# SOIL_WATER.net
KiCad netlist of a schematic drawn in EAGLE
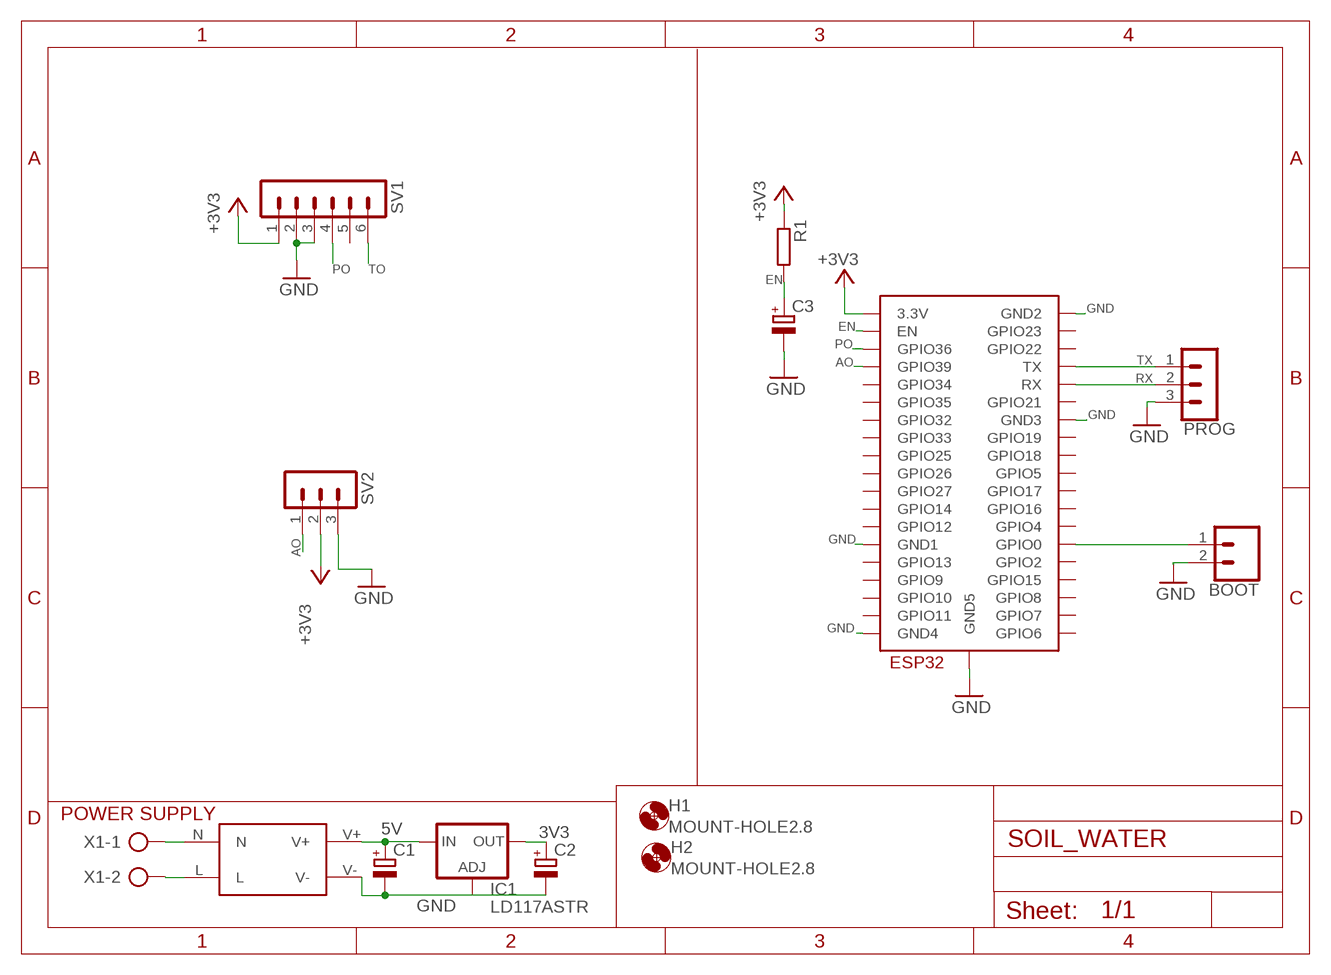
[diagram p0: schematic, sheet 1]

(export (version "E")
  (design (tool "Eeschema 10.0.6"))
  (components
    (comp (ref "BOOT")
      (value "CONN_02")
      (footprint "eagle-import:1X02")
      (libsource (lib "eagle-import") (part "CONN_02"))
    )
    (comp (ref "C1")
      (value "CPOL-EUE1.8-4")
      (footprint "eagle-import:E1,8-4")
      (libsource (lib "eagle-import") (part "CPOL-EUE1.8-4"))
    )
    (comp (ref "C2")
      (value "CPOL-EUE1.8-4")
      (footprint "eagle-import:E1,8-4")
      (libsource (lib "eagle-import") (part "CPOL-EUE1.8-4"))
    )
    (comp (ref "C3")
      (value "CPOL-EUE1.8-4")
      (footprint "eagle-import:E1,8-4")
      (libsource (lib "eagle-import") (part "CPOL-EUE1.8-4"))
    )
    (comp (ref "H1")
      (value "MOUNT-HOLE2.8")
      (footprint "eagle-import:2,8")
      (libsource (lib "eagle-import") (part "MOUNT-HOLE2.8"))
    )
    (comp (ref "H2")
      (value "MOUNT-HOLE2.8")
      (footprint "eagle-import:2,8")
      (libsource (lib "eagle-import") (part "MOUNT-HOLE2.8"))
    )
    (comp (ref "IC1")
      (value "LD117ASTR")
      (footprint "eagle-import:SOT223")
      (libsource (lib "eagle-import") (part "LD117A?STR"))
    )
    (comp (ref "PROG")
      (value "MA03-1")
      (footprint "eagle-import:MA03-1")
      (libsource (lib "eagle-import") (part "MA03-1"))
    )
    (comp (ref "R1")
      (value "R-EU_0204/7")
      (footprint "eagle-import:0204_7")
      (libsource (lib "eagle-import") (part "R-EU_0204/7"))
    )
    (comp (ref "SV1")
      (value "MA06-1")
      (footprint "eagle-import:MA06-1")
      (libsource (lib "eagle-import") (part "MA06-1"))
    )
    (comp (ref "SV2")
      (value "MA03-1")
      (footprint "eagle-import:MA03-1")
      (libsource (lib "eagle-import") (part "MA03-1"))
    )
    (comp (ref "U$1")
      (value "ESP32-WROOM")
      (footprint "eagle-import:ESP32-WROOM")
      (libsource (lib "eagle-import") (part "ESP32-WROOM"))
    )
    (comp (ref "U$2")
      (value "HLK-PM01")
      (footprint "eagle-import:HLK-PM01-PAK")
      (fields (field (name "MF") "Hi-link") (field (name "MP") "hlk-pm01"))
      (libsource (lib "eagle-import") (part "HLK-PM01"))
    )
    (comp (ref "X1")
      (value "AK500/2")
      (footprint "eagle-import:AK500_2")
      (libsource (lib "eagle-import") (part "AK500/2"))
    )
  )
  (nets
    (net (code "1") (name "+3V3") (class "Default")
      (node (ref "R1") (pin "1") (pinfunction "1_1") (pintype "passive"))
      (node (ref "SV1") (pin "1") (pinfunction "1_1") (pintype "passive"))
      (node (ref "SV2") (pin "2") (pinfunction "2_2") (pintype "passive"))
      (node (ref "U$1") (pin "3V3") (pinfunction "3.3V_3V3") (pintype "bidirectional"))
    )
    (net (code "2") (name "/3V3") (class "Default")
      (node (ref "C2") (pin "+") (pinfunction "+_+") (pintype "passive"))
      (node (ref "IC1") (pin "4") (pinfunction "OUT_4") (pintype "passive"))
    )
    (net (code "3") (name "/5V") (class "Default")
      (node (ref "C1") (pin "+") (pinfunction "+_+") (pintype "passive"))
      (node (ref "IC1") (pin "3") (pinfunction "IN_3") (pintype "input"))
      (node (ref "U$2") (pin "V+") (pinfunction "V+_V+") (pintype "bidirectional"))
    )
    (net (code "4") (name "/AO") (class "Default")
      (node (ref "SV2") (pin "1") (pinfunction "1_1") (pintype "passive"))
      (node (ref "U$1") (pin "SENSOR_VN") (pinfunction "GPIO39_SENSOR_VN") (pintype "bidirectional"))
    )
    (net (code "5") (name "/EN") (class "Default")
      (node (ref "C3") (pin "+") (pinfunction "+_+") (pintype "passive"))
      (node (ref "R1") (pin "2") (pinfunction "2_2") (pintype "passive"))
      (node (ref "U$1") (pin "EN") (pinfunction "EN_EN") (pintype "bidirectional"))
    )
    (net (code "6") (name "/PO") (class "Default")
      (node (ref "SV1") (pin "4") (pinfunction "4_4") (pintype "passive"))
      (node (ref "U$1") (pin "SENSOR_VP") (pinfunction "GPIO36_SENSOR_VP") (pintype "bidirectional"))
    )
    (net (code "7") (name "/RX") (class "Default")
      (node (ref "PROG") (pin "2") (pinfunction "2_2") (pintype "passive"))
      (node (ref "U$1") (pin "RX") (pinfunction "RX_RX") (pintype "bidirectional"))
    )
    (net (code "8") (name "/TO") (class "Default")
      (node (ref "SV1") (pin "6") (pinfunction "6_6") (pintype "passive"))
    )
    (net (code "9") (name "/TX") (class "Default")
      (node (ref "PROG") (pin "1") (pinfunction "1_1") (pintype "passive"))
      (node (ref "U$1") (pin "TX") (pinfunction "TX_TX") (pintype "bidirectional"))
    )
    (net (code "10") (name "GND") (class "Default")
      (node (ref "BOOT") (pin "2") (pinfunction "2_2") (pintype "passive"))
      (node (ref "C1") (pin "-") (pinfunction "-_-") (pintype "passive"))
      (node (ref "C2") (pin "-") (pinfunction "-_-") (pintype "passive"))
      (node (ref "C3") (pin "-") (pinfunction "-_-") (pintype "passive"))
      (node (ref "IC1") (pin "1") (pinfunction "ADJ_1") (pintype "input"))
      (node (ref "PROG") (pin "3") (pinfunction "3_3") (pintype "passive"))
      (node (ref "SV1") (pin "2") (pinfunction "2_2") (pintype "passive"))
      (node (ref "SV1") (pin "3") (pinfunction "3_3") (pintype "passive"))
      (node (ref "SV2") (pin "3") (pinfunction "3_3") (pintype "passive"))
      (node (ref "U$1") (pin "GND1") (pinfunction "GND1_GND1") (pintype "bidirectional"))
      (node (ref "U$1") (pin "GND2") (pinfunction "GND2_GND2") (pintype "bidirectional"))
      (node (ref "U$1") (pin "GND3") (pinfunction "GND3_GND3") (pintype "bidirectional"))
      (node (ref "U$1") (pin "GND4") (pinfunction "GND4_GND4") (pintype "bidirectional"))
      (node (ref "U$1") (pin "GND5") (pinfunction "GND5_GND5") (pintype "bidirectional"))
      (node (ref "U$2") (pin "V-") (pinfunction "V-_V-") (pintype "bidirectional"))
    )
    (net (code "11") (name "Net-(U$1-GPIO0)") (class "Default")
      (node (ref "BOOT") (pin "1") (pinfunction "1_1") (pintype "passive"))
      (node (ref "U$1") (pin "IO0") (pinfunction "GPIO0_IO0") (pintype "bidirectional"))
    )
    (net (code "12") (name "Net-(X1A-KL)") (class "Default")
      (node (ref "U$2") (pin "N") (pinfunction "N_N") (pintype "bidirectional"))
      (node (ref "X1") (pin "1") (pinfunction "KL_1") (pintype "passive"))
    )
    (net (code "13") (name "Net-(X1B-KL)") (class "Default")
      (node (ref "U$2") (pin "L") (pinfunction "L_L") (pintype "bidirectional"))
      (node (ref "X1") (pin "2") (pinfunction "KL_2") (pintype "passive"))
    )
    (net (code "14") (name "unconnected-(SV1-Pad5)") (class "Default")
      (node (ref "SV1") (pin "5") (pinfunction "5_5") (pintype "passive"))
    )
    (net (code "15") (name "unconnected-(U$1-GPIO2-PadIO2)") (class "Default")
      (node (ref "U$1") (pin "IO2") (pinfunction "GPIO2_IO2") (pintype "bidirectional"))
    )
    (net (code "16") (name "unconnected-(U$1-GPIO4-PadIO4)") (class "Default")
      (node (ref "U$1") (pin "IO4") (pinfunction "GPIO4_IO4") (pintype "bidirectional"))
    )
    (net (code "17") (name "unconnected-(U$1-GPIO5-PadIO5)") (class "Default")
      (node (ref "U$1") (pin "IO5") (pinfunction "GPIO5_IO5") (pintype "bidirectional"))
    )
    (net (code "18") (name "unconnected-(U$1-GPIO6-PadCLK)") (class "Default")
      (node (ref "U$1") (pin "CLK") (pinfunction "GPIO6_CLK") (pintype "bidirectional"))
    )
    (net (code "19") (name "unconnected-(U$1-GPIO7-PadSD0)") (class "Default")
      (node (ref "U$1") (pin "SD0") (pinfunction "GPIO7_SD0") (pintype "bidirectional"))
    )
    (net (code "20") (name "unconnected-(U$1-GPIO8-PadSD1)") (class "Default")
      (node (ref "U$1") (pin "SD1") (pinfunction "GPIO8_SD1") (pintype "bidirectional"))
    )
    (net (code "21") (name "unconnected-(U$1-GPIO9-PadSD2)") (class "Default")
      (node (ref "U$1") (pin "SD2") (pinfunction "GPIO9_SD2") (pintype "bidirectional"))
    )
    (net (code "22") (name "unconnected-(U$1-GPIO10-PadSD3)") (class "Default")
      (node (ref "U$1") (pin "SD3") (pinfunction "GPIO10_SD3") (pintype "bidirectional"))
    )
    (net (code "23") (name "unconnected-(U$1-GPIO11-PadCMD)") (class "Default")
      (node (ref "U$1") (pin "CMD") (pinfunction "GPIO11_CMD") (pintype "bidirectional"))
    )
    (net (code "24") (name "unconnected-(U$1-GPIO12-PadIO12)") (class "Default")
      (node (ref "U$1") (pin "IO12") (pinfunction "GPIO12_IO12") (pintype "bidirectional"))
    )
    (net (code "25") (name "unconnected-(U$1-GPIO13-PadIO13)") (class "Default")
      (node (ref "U$1") (pin "IO13") (pinfunction "GPIO13_IO13") (pintype "bidirectional"))
    )
    (net (code "26") (name "unconnected-(U$1-GPIO14-PadIO14)") (class "Default")
      (node (ref "U$1") (pin "IO14") (pinfunction "GPIO14_IO14") (pintype "bidirectional"))
    )
    (net (code "27") (name "unconnected-(U$1-GPIO15-PadIO15)") (class "Default")
      (node (ref "U$1") (pin "IO15") (pinfunction "GPIO15_IO15") (pintype "bidirectional"))
    )
    (net (code "28") (name "unconnected-(U$1-GPIO16-PadIO16)") (class "Default")
      (node (ref "U$1") (pin "IO16") (pinfunction "GPIO16_IO16") (pintype "bidirectional"))
    )
    (net (code "29") (name "unconnected-(U$1-GPIO17-PadIO17)") (class "Default")
      (node (ref "U$1") (pin "IO17") (pinfunction "GPIO17_IO17") (pintype "bidirectional"))
    )
    (net (code "30") (name "unconnected-(U$1-GPIO18-PadIO18)") (class "Default")
      (node (ref "U$1") (pin "IO18") (pinfunction "GPIO18_IO18") (pintype "bidirectional"))
    )
    (net (code "31") (name "unconnected-(U$1-GPIO19-PadIO19)") (class "Default")
      (node (ref "U$1") (pin "IO19") (pinfunction "GPIO19_IO19") (pintype "bidirectional"))
    )
    (net (code "32") (name "unconnected-(U$1-GPIO21-PadIO21)") (class "Default")
      (node (ref "U$1") (pin "IO21") (pinfunction "GPIO21_IO21") (pintype "bidirectional"))
    )
    (net (code "33") (name "unconnected-(U$1-GPIO22-PadIO22)") (class "Default")
      (node (ref "U$1") (pin "IO22") (pinfunction "GPIO22_IO22") (pintype "bidirectional"))
    )
    (net (code "34") (name "unconnected-(U$1-GPIO23-PadIO23)") (class "Default")
      (node (ref "U$1") (pin "IO23") (pinfunction "GPIO23_IO23") (pintype "bidirectional"))
    )
    (net (code "35") (name "unconnected-(U$1-GPIO25-PadIO25)") (class "Default")
      (node (ref "U$1") (pin "IO25") (pinfunction "GPIO25_IO25") (pintype "bidirectional"))
    )
    (net (code "36") (name "unconnected-(U$1-GPIO26-PadIO26)") (class "Default")
      (node (ref "U$1") (pin "IO26") (pinfunction "GPIO26_IO26") (pintype "bidirectional"))
    )
    (net (code "37") (name "unconnected-(U$1-GPIO27-PadIO27)") (class "Default")
      (node (ref "U$1") (pin "IO27") (pinfunction "GPIO27_IO27") (pintype "bidirectional"))
    )
    (net (code "38") (name "unconnected-(U$1-GPIO32-PadIO32)") (class "Default")
      (node (ref "U$1") (pin "IO32") (pinfunction "GPIO32_IO32") (pintype "bidirectional"))
    )
    (net (code "39") (name "unconnected-(U$1-GPIO33-PadIO33)") (class "Default")
      (node (ref "U$1") (pin "IO33") (pinfunction "GPIO33_IO33") (pintype "bidirectional"))
    )
    (net (code "40") (name "unconnected-(U$1-GPIO34-PadIO34)") (class "Default")
      (node (ref "U$1") (pin "IO34") (pinfunction "GPIO34_IO34") (pintype "bidirectional"))
    )
    (net (code "41") (name "unconnected-(U$1-GPIO35-PadIO35)") (class "Default")
      (node (ref "U$1") (pin "IO35") (pinfunction "GPIO35_IO35") (pintype "bidirectional"))
    )
  )
)
